# BalanceCar.net
KiCad netlist of a schematic drawn in Altium Designer
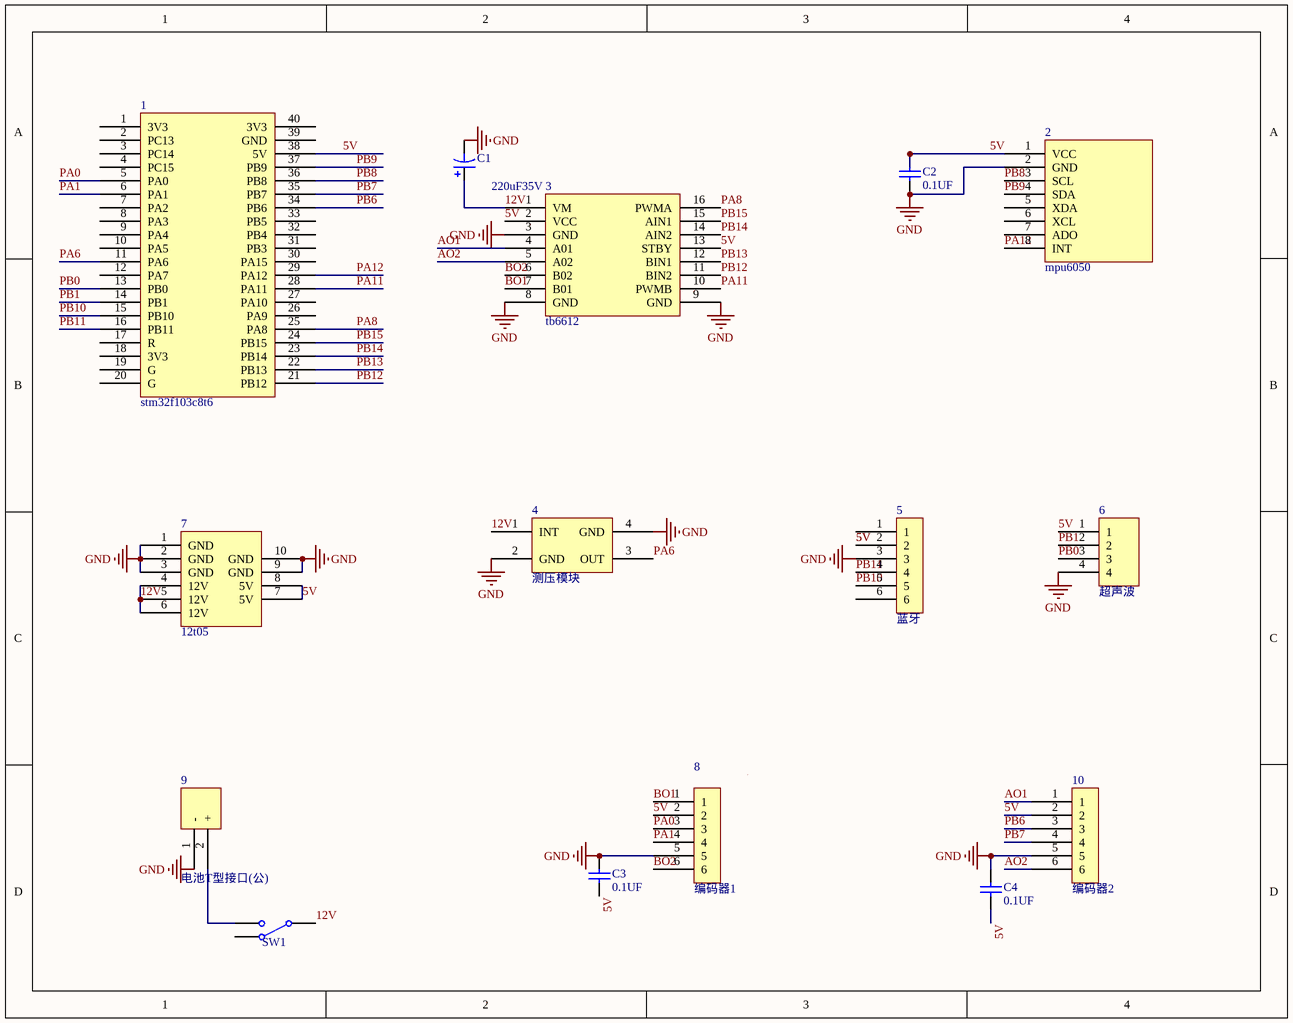
[diagram p0: BalanceCar.SchDoc]

(export (version "E")
  (design (tool "Eeschema 10.0.6"))
  (components
    (comp (ref "1")
      (value "stm32f103c8t6")
      (footprint "STM32F103C8T6")
      (libsource (lib "Schlib1") (part "stm32f103c8t6"))
    )
    (comp (ref "2") (value "mpu6050") (footprint "6050new") (libsource (lib "Schlib1") (part "mpu6050")))
    (comp (ref "3") (value "tb6612") (footprint "TB6612DIP") (libsource (lib "Schlib1") (part "tb6612")))
    (comp (ref "4") (value "测压模块") (footprint "DF - 3") (libsource (lib "Schlib1") (part "测压模块")))
    (comp (ref "5") (value "蓝牙") (footprint "HDR1X6 - XH弯") (libsource (lib "Schlib1") (part "蓝牙")))
    (comp (ref "6") (value "超声波") (footprint "HDR1X4") (libsource (lib "Schlib1") (part "超声波")))
    (comp (ref "7") (value "12t05") (footprint "稳压12T05") (libsource (lib "Schlib1") (part "12t05")))
    (comp (ref "8") (value "编码器1") (footprint "1*6弯排母") (libsource (lib "Schlib1") (part "编码器1")))
    (comp (ref "9") (value "电池T型接口(公)") (footprint "T HEAD") (libsource (lib "Schlib1") (part "电池T型接口(公)")))
    (comp (ref "10") (value "编码器2") (footprint "1*6弯排母") (libsource (lib "Schlib1") (part "编码器2")))
    (comp (ref "C1")
      (value "220uF35V")
      (footprint "CAP-820uF-6.3V")
      (description "Polarized Capacitor (Radial)")
      (fields (field (name "PUBLISHER") "Altium Limited"))
      (libsource (lib "Miscellaneous Devices") (part "Cap Pol1"))
    )
    (comp (ref "C2")
      (value "0.1UF")
      (footprint "Cap-CP")
      (description "Capacitor")
      (libsource (lib "Simulation Generic Components") (part "Capacitor"))
    )
    (comp (ref "C3")
      (value "0.1UF")
      (footprint "Cap-CP")
      (description "Capacitor")
      (libsource (lib "Simulation Generic Components") (part "Capacitor"))
    )
    (comp (ref "C4")
      (value "0.1UF")
      (footprint "Cap-CP")
      (description "Capacitor")
      (libsource (lib "Simulation Generic Components") (part "Capacitor"))
    )
    (comp (ref "SW1")
      (value "Single-Pole, Double-Throw Switch")
      (footprint "SS12d11拨动电源开关")
      (libsource (lib "Simulation Generic Components") (part "SPDT SW"))
    )
  )
  (nets
    (net (code "1") (name "/5V") (class "Default")
      (node (ref "1") (pin "38") (pinfunction "5V_38") (pintype "passive"))
      (node (ref "10") (pin "2") (pinfunction "2_2") (pintype "passive"))
      (node (ref "2") (pin "1") (pinfunction "VCC_1") (pintype "passive"))
      (node (ref "3") (pin "13") (pinfunction "STBY_13") (pintype "passive"))
      (node (ref "3") (pin "2") (pinfunction "VCC_2") (pintype "passive"))
      (node (ref "5") (pin "2") (pinfunction "2_2") (pintype "passive"))
      (node (ref "6") (pin "1") (pinfunction "1_1") (pintype "passive"))
      (node (ref "7") (pin "7") (pinfunction "5V_7") (pintype "passive"))
      (node (ref "7") (pin "8") (pinfunction "5V_8") (pintype "passive"))
      (node (ref "8") (pin "2") (pinfunction "2_2") (pintype "passive"))
      (node (ref "C2") (pin "1") (pinfunction "1_1") (pintype "passive"))
      (node (ref "C3") (pin "2") (pinfunction "2_2") (pintype "passive"))
      (node (ref "C4") (pin "1") (pinfunction "1_1") (pintype "passive"))
    )
    (net (code "2") (name "/12V") (class "Default")
      (node (ref "3") (pin "1") (pinfunction "VM_1") (pintype "passive"))
      (node (ref "4") (pin "1") (pinfunction "INT_1") (pintype "passive"))
      (node (ref "7") (pin "4") (pinfunction "12V_4") (pintype "passive"))
      (node (ref "7") (pin "5") (pinfunction "12V_5") (pintype "passive"))
      (node (ref "7") (pin "6") (pinfunction "12V_6") (pintype "passive"))
      (node (ref "C1") (pin "1") (pinfunction "1_1") (pintype "passive"))
      (node (ref "SW1") (pin "1") (pinfunction "1_1") (pintype "passive"))
    )
    (net (code "3") (name "/AO1") (class "Default")
      (node (ref "10") (pin "1") (pinfunction "1_1") (pintype "passive"))
      (node (ref "3") (pin "4") (pinfunction "A01_4") (pintype "passive"))
    )
    (net (code "4") (name "/AO2") (class "Default")
      (node (ref "10") (pin "6") (pinfunction "6_6") (pintype "passive"))
      (node (ref "3") (pin "5") (pinfunction "A02_5") (pintype "passive"))
    )
    (net (code "5") (name "/BO1") (class "Default")
      (node (ref "3") (pin "7") (pinfunction "B01_7") (pintype "passive"))
      (node (ref "8") (pin "1") (pinfunction "1_1") (pintype "passive"))
    )
    (net (code "6") (name "/BO2") (class "Default")
      (node (ref "3") (pin "6") (pinfunction "B02_6") (pintype "passive"))
      (node (ref "8") (pin "6") (pinfunction "6_6") (pintype "passive"))
    )
    (net (code "7") (name "/PA0") (class "Default")
      (node (ref "1") (pin "5") (pinfunction "PA0_5") (pintype "passive"))
      (node (ref "8") (pin "3") (pinfunction "3_3") (pintype "passive"))
    )
    (net (code "8") (name "/PA1") (class "Default")
      (node (ref "1") (pin "6") (pinfunction "PA1_6") (pintype "passive"))
      (node (ref "8") (pin "4") (pinfunction "4_4") (pintype "passive"))
    )
    (net (code "9") (name "/PA6") (class "Default")
      (node (ref "1") (pin "11") (pinfunction "PA6_11") (pintype "passive"))
      (node (ref "4") (pin "3") (pinfunction "OUT_3") (pintype "passive"))
    )
    (net (code "10") (name "/PA8") (class "Default")
      (node (ref "1") (pin "25") (pinfunction "PA8_25") (pintype "passive"))
      (node (ref "3") (pin "16") (pinfunction "PWMA_16") (pintype "passive"))
    )
    (net (code "11") (name "/PA11") (class "Default")
      (node (ref "1") (pin "28") (pinfunction "PA11_28") (pintype "passive"))
      (node (ref "3") (pin "10") (pinfunction "PWMB_10") (pintype "passive"))
    )
    (net (code "12") (name "/PA12") (class "Default")
      (node (ref "1") (pin "29") (pinfunction "PA12_29") (pintype "passive"))
      (node (ref "2") (pin "8") (pinfunction "INT_8") (pintype "passive"))
    )
    (net (code "13") (name "/PB0") (class "Default")
      (node (ref "1") (pin "13") (pinfunction "PB0_13") (pintype "passive"))
      (node (ref "6") (pin "3") (pinfunction "3_3") (pintype "passive"))
    )
    (net (code "14") (name "/PB1") (class "Default")
      (node (ref "1") (pin "14") (pinfunction "PB1_14") (pintype "passive"))
      (node (ref "6") (pin "2") (pinfunction "2_2") (pintype "passive"))
    )
    (net (code "15") (name "/PB6") (class "Default")
      (node (ref "1") (pin "34") (pinfunction "PB6_34") (pintype "passive"))
      (node (ref "10") (pin "3") (pinfunction "3_3") (pintype "passive"))
    )
    (net (code "16") (name "/PB7") (class "Default")
      (node (ref "1") (pin "35") (pinfunction "PB7_35") (pintype "passive"))
      (node (ref "10") (pin "4") (pinfunction "4_4") (pintype "passive"))
    )
    (net (code "17") (name "/PB8") (class "Default")
      (node (ref "1") (pin "36") (pinfunction "PB8_36") (pintype "passive"))
      (node (ref "2") (pin "3") (pinfunction "SCL_3") (pintype "passive"))
    )
    (net (code "18") (name "/PB9") (class "Default")
      (node (ref "1") (pin "37") (pinfunction "PB9_37") (pintype "passive"))
      (node (ref "2") (pin "4") (pinfunction "SDA_4") (pintype "passive"))
    )
    (net (code "19") (name "/PB10") (class "Default")
      (node (ref "1") (pin "15") (pinfunction "PB10_15") (pintype "passive"))
      (node (ref "5") (pin "5") (pinfunction "5_5") (pintype "passive"))
    )
    (net (code "20") (name "/PB11") (class "Default")
      (node (ref "1") (pin "16") (pinfunction "PB11_16") (pintype "passive"))
      (node (ref "5") (pin "4") (pinfunction "4_4") (pintype "passive"))
    )
    (net (code "21") (name "/PB12") (class "Default")
      (node (ref "1") (pin "21") (pinfunction "PB12_21") (pintype "passive"))
      (node (ref "3") (pin "11") (pinfunction "BIN2_11") (pintype "passive"))
    )
    (net (code "22") (name "/PB13") (class "Default")
      (node (ref "1") (pin "22") (pinfunction "PB13_22") (pintype "passive"))
      (node (ref "3") (pin "12") (pinfunction "BIN1_12") (pintype "passive"))
    )
    (net (code "23") (name "/PB14") (class "Default")
      (node (ref "1") (pin "23") (pinfunction "PB14_23") (pintype "passive"))
      (node (ref "3") (pin "14") (pinfunction "AIN2_14") (pintype "passive"))
    )
    (net (code "24") (name "/PB15") (class "Default")
      (node (ref "1") (pin "24") (pinfunction "PB15_24") (pintype "passive"))
      (node (ref "3") (pin "15") (pinfunction "AIN1_15") (pintype "passive"))
    )
    (net (code "25") (name "GND") (class "Default")
      (node (ref "10") (pin "5") (pinfunction "5_5") (pintype "passive"))
      (node (ref "2") (pin "2") (pinfunction "GND_2") (pintype "passive"))
      (node (ref "3") (pin "3") (pinfunction "GND_3") (pintype "passive"))
      (node (ref "3") (pin "8") (pinfunction "GND_8") (pintype "passive"))
      (node (ref "3") (pin "9") (pinfunction "GND_9") (pintype "passive"))
      (node (ref "4") (pin "2") (pinfunction "GND_2") (pintype "passive"))
      (node (ref "4") (pin "4") (pinfunction "GND_4") (pintype "passive"))
      (node (ref "5") (pin "3") (pinfunction "3_3") (pintype "passive"))
      (node (ref "6") (pin "4") (pinfunction "4_4") (pintype "passive"))
      (node (ref "7") (pin "1") (pinfunction "GND_1") (pintype "passive"))
      (node (ref "7") (pin "10") (pinfunction "GND_10") (pintype "passive"))
      (node (ref "7") (pin "2") (pinfunction "GND_2") (pintype "passive"))
      (node (ref "7") (pin "3") (pinfunction "GND_3") (pintype "passive"))
      (node (ref "7") (pin "9") (pinfunction "GND_9") (pintype "passive"))
      (node (ref "8") (pin "5") (pinfunction "5_5") (pintype "passive"))
      (node (ref "9") (pin "1") (pinfunction "-_1") (pintype "passive"))
      (node (ref "C1") (pin "2") (pinfunction "2_2") (pintype "passive"))
      (node (ref "C2") (pin "2") (pinfunction "2_2") (pintype "passive"))
      (node (ref "C3") (pin "1") (pinfunction "1_1") (pintype "passive"))
      (node (ref "C4") (pin "2") (pinfunction "2_2") (pintype "passive"))
    )
    (net (code "26") (name "Net-(9-+)") (class "Default")
      (node (ref "9") (pin "2") (pinfunction "+_2") (pintype "passive"))
      (node (ref "SW1") (pin "2") (pinfunction "2_2") (pintype "passive"))
    )
    (net (code "27") (name "unconnected-(1-3V3-Pad1)") (class "Default")
      (node (ref "1") (pin "1") (pinfunction "3V3_1") (pintype "passive"))
    )
    (net (code "28") (name "unconnected-(1-3V3-Pad18)") (class "Default")
      (node (ref "1") (pin "18") (pinfunction "3V3_18") (pintype "passive"))
    )
    (net (code "29") (name "unconnected-(1-3V3-Pad40)") (class "Default")
      (node (ref "1") (pin "40") (pinfunction "3V3_40") (pintype "passive"))
    )
    (net (code "30") (name "unconnected-(1-G-Pad19)") (class "Default")
      (node (ref "1") (pin "19") (pinfunction "G_19") (pintype "passive"))
    )
    (net (code "31") (name "unconnected-(1-G-Pad20)") (class "Default")
      (node (ref "1") (pin "20") (pinfunction "G_20") (pintype "passive"))
    )
    (net (code "32") (name "unconnected-(1-GND-Pad39)") (class "Default")
      (node (ref "1") (pin "39") (pinfunction "GND_39") (pintype "passive"))
    )
    (net (code "33") (name "unconnected-(1-PA2-Pad7)") (class "Default")
      (node (ref "1") (pin "7") (pinfunction "PA2_7") (pintype "passive"))
    )
    (net (code "34") (name "unconnected-(1-PA3-Pad8)") (class "Default")
      (node (ref "1") (pin "8") (pinfunction "PA3_8") (pintype "passive"))
    )
    (net (code "35") (name "unconnected-(1-PA4-Pad9)") (class "Default")
      (node (ref "1") (pin "9") (pinfunction "PA4_9") (pintype "passive"))
    )
    (net (code "36") (name "unconnected-(1-PA5-Pad10)") (class "Default")
      (node (ref "1") (pin "10") (pinfunction "PA5_10") (pintype "passive"))
    )
    (net (code "37") (name "unconnected-(1-PA7-Pad12)") (class "Default")
      (node (ref "1") (pin "12") (pinfunction "PA7_12") (pintype "passive"))
    )
    (net (code "38") (name "unconnected-(1-PA9-Pad26)") (class "Default")
      (node (ref "1") (pin "26") (pinfunction "PA9_26") (pintype "passive"))
    )
    (net (code "39") (name "unconnected-(1-PA10-Pad27)") (class "Default")
      (node (ref "1") (pin "27") (pinfunction "PA10_27") (pintype "passive"))
    )
    (net (code "40") (name "unconnected-(1-PA15-Pad30)") (class "Default")
      (node (ref "1") (pin "30") (pinfunction "PA15_30") (pintype "passive"))
    )
    (net (code "41") (name "unconnected-(1-PB3-Pad31)") (class "Default")
      (node (ref "1") (pin "31") (pinfunction "PB3_31") (pintype "passive"))
    )
    (net (code "42") (name "unconnected-(1-PB4-Pad32)") (class "Default")
      (node (ref "1") (pin "32") (pinfunction "PB4_32") (pintype "passive"))
    )
    (net (code "43") (name "unconnected-(1-PB5-Pad33)") (class "Default")
      (node (ref "1") (pin "33") (pinfunction "PB5_33") (pintype "passive"))
    )
    (net (code "44") (name "unconnected-(1-PC13-Pad2)") (class "Default")
      (node (ref "1") (pin "2") (pinfunction "PC13_2") (pintype "passive"))
    )
    (net (code "45") (name "unconnected-(1-PC14-Pad3)") (class "Default")
      (node (ref "1") (pin "3") (pinfunction "PC14_3") (pintype "passive"))
    )
    (net (code "46") (name "unconnected-(1-PC15-Pad4)") (class "Default")
      (node (ref "1") (pin "4") (pinfunction "PC15_4") (pintype "passive"))
    )
    (net (code "47") (name "unconnected-(1-R-Pad17)") (class "Default")
      (node (ref "1") (pin "17") (pinfunction "R_17") (pintype "passive"))
    )
    (net (code "48") (name "unconnected-(2-ADO-Pad7)") (class "Default")
      (node (ref "2") (pin "7") (pinfunction "ADO_7") (pintype "passive"))
    )
    (net (code "49") (name "unconnected-(2-XCL-Pad6)") (class "Default")
      (node (ref "2") (pin "6") (pinfunction "XCL_6") (pintype "passive"))
    )
    (net (code "50") (name "unconnected-(2-XDA-Pad5)") (class "Default")
      (node (ref "2") (pin "5") (pinfunction "XDA_5") (pintype "passive"))
    )
    (net (code "51") (name "unconnected-(5-Pad1)") (class "Default")
      (node (ref "5") (pin "1") (pinfunction "1_1") (pintype "passive"))
    )
    (net (code "52") (name "unconnected-(5-Pad6)") (class "Default")
      (node (ref "5") (pin "6") (pinfunction "6_6") (pintype "passive"))
    )
    (net (code "53") (name "unconnected-(SW1-Pad3)") (class "Default")
      (node (ref "SW1") (pin "3") (pinfunction "3_3") (pintype "passive"))
    )
  )
)
